# InkTime.net
KiCad netlist of a schematic drawn in EAGLE
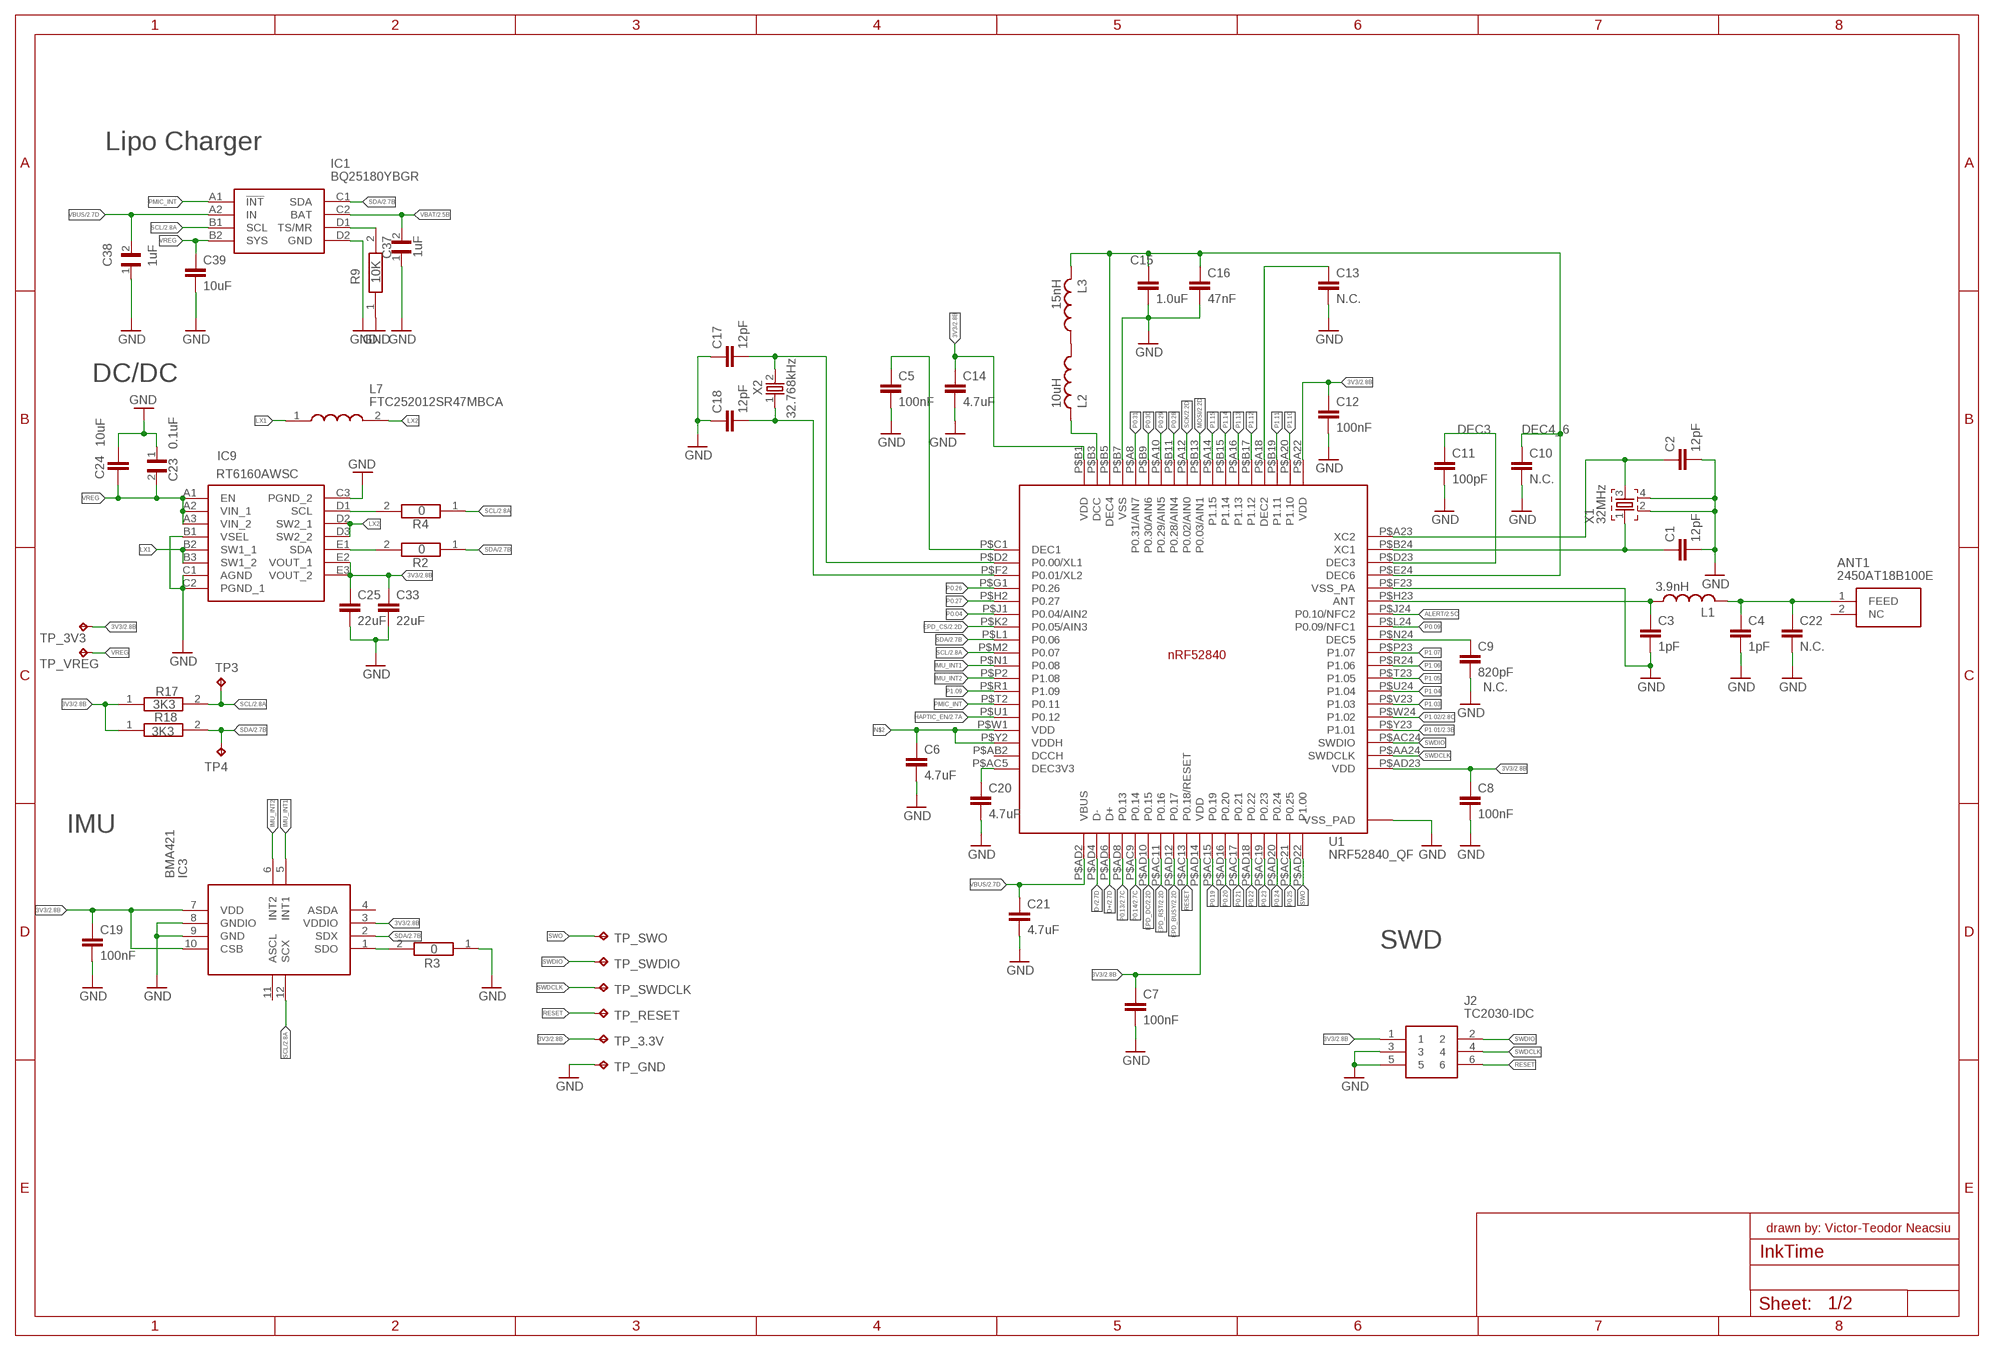
[diagram p0: schematic, sheet 1]
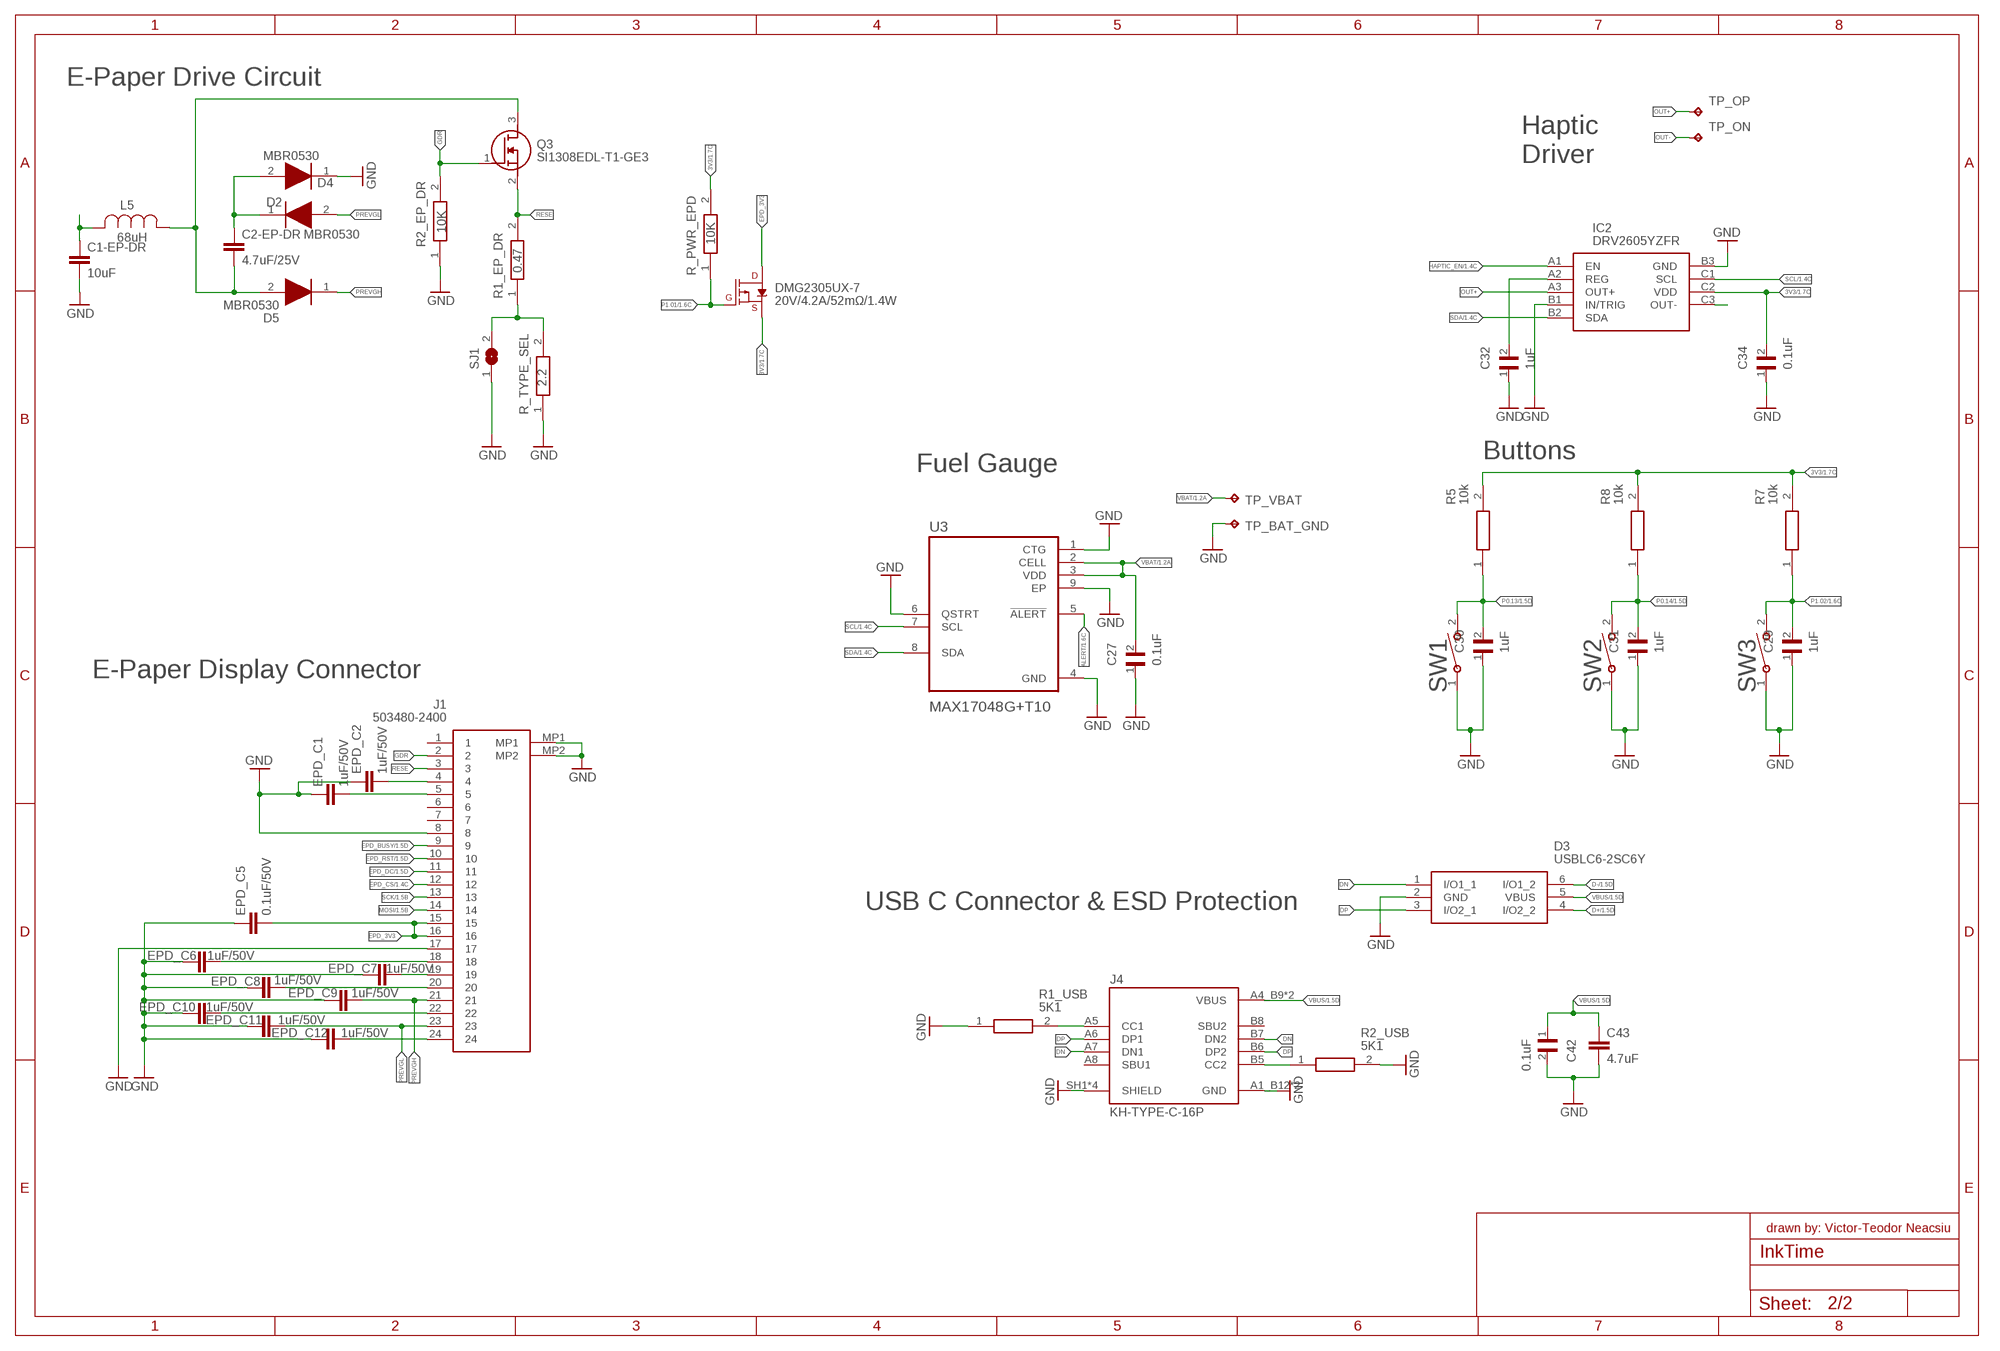
[diagram p1: schematic, sheet 2]

(export (version "E")
  (design (tool "Eeschema 10.0.6"))
  (components
    (comp (ref "C1-EP-DR")
      (value "10uF")
      (footprint "eagle-import:NORDIC_NRF_3_RESC0402_L")
      (libsource (lib "eagle-import") (part "NORDIC_NRF_3_CAPACITOR_0402_L"))
    )
    (comp (ref "C2-EP-DR")
      (value "4.7uF/25V")
      (footprint "eagle-import:NORDIC_NRF_3_RESC0402_L")
      (libsource (lib "eagle-import") (part "NORDIC_NRF_3_CAPACITOR_0402_L"))
    )
    (comp (ref "C27")
      (value "0.1uF")
      (footprint "eagle-import:GRM011R60J152KE01L_2_CAPC0201X13N")
      (fields (field (name "MF") "Murata") (field (name "MP") "GRM011R60J152KE01L"))
      (libsource (lib "eagle-import") (part "GRM011R60J152KE01L_2_GRM011R60J152KE01L"))
    )
    (comp (ref "C29")
      (value "1uF")
      (footprint "eagle-import:GRM011R60J152KE01L_2_CAPC0201X13N")
      (fields (field (name "MF") "Murata") (field (name "MP") "GRM011R60J152KE01L"))
      (libsource (lib "eagle-import") (part "GRM011R60J152KE01L_2_GRM011R60J152KE01L"))
    )
    (comp (ref "C30")
      (value "1uF")
      (footprint "eagle-import:GRM011R60J152KE01L_2_CAPC0201X13N")
      (fields (field (name "MF") "Murata") (field (name "MP") "GRM011R60J152KE01L"))
      (libsource (lib "eagle-import") (part "GRM011R60J152KE01L_2_GRM011R60J152KE01L"))
    )
    (comp (ref "C31")
      (value "1uF")
      (footprint "eagle-import:GRM011R60J152KE01L_2_CAPC0201X13N")
      (fields (field (name "MF") "Murata") (field (name "MP") "GRM011R60J152KE01L"))
      (libsource (lib "eagle-import") (part "GRM011R60J152KE01L_2_GRM011R60J152KE01L"))
    )
    (comp (ref "C32")
      (value "1uF")
      (footprint "eagle-import:GRM011R60J152KE01L_2_CAPC0201X13N")
      (fields (field (name "MF") "Murata") (field (name "MP") "GRM011R60J152KE01L"))
      (libsource (lib "eagle-import") (part "GRM011R60J152KE01L_2_GRM011R60J152KE01L"))
    )
    (comp (ref "C34")
      (value "0.1uF")
      (footprint "eagle-import:GRM011R60J152KE01L_2_CAPC0201X13N")
      (fields (field (name "MF") "Murata") (field (name "MP") "GRM011R60J152KE01L"))
      (libsource (lib "eagle-import") (part "GRM011R60J152KE01L_2_GRM011R60J152KE01L"))
    )
    (comp (ref "C42")
      (value "0.1uF")
      (footprint "eagle-import:GRM011R60J152KE01L_2_CAPC0201X13N")
      (fields (field (name "MF") "Murata") (field (name "MP") "GRM011R60J152KE01L"))
      (libsource (lib "eagle-import") (part "GRM011R60J152KE01L_2_GRM011R60J152KE01L"))
    )
    (comp (ref "C43")
      (value "4.7uF")
      (footprint "eagle-import:NORDIC_NRF_3_RESC0402_L")
      (libsource (lib "eagle-import") (part "NORDIC_NRF_3_CAPACITOR_0402_L"))
    )
    (comp (ref "D2")
      (value "MBR0530")
      (footprint "eagle-import:ESP32_C6_LIBRARY_5_SOD3716X135N")
      (fields (field (name "MF") "ON Semiconductor"))
      (libsource (lib "eagle-import") (part "ESP32_C6_LIBRARY_5_MBR0530"))
    )
    (comp (ref "D3")
      (value "USBLC6-2SC6Y")
      (footprint "eagle-import:ESP32_C6_LIBRARY_3_SOT95P280X145-6N")
      (fields (field (name "MF") "STMicroelectronics"))
      (libsource (lib "eagle-import") (part "ESP32_C6_LIBRARY_3_USBLC6-2SC6Y"))
    )
    (comp (ref "D4")
      (value "MBR0530")
      (footprint "eagle-import:ESP32_C6_LIBRARY_5_SOD3716X135N")
      (fields (field (name "MF") "ON Semiconductor"))
      (libsource (lib "eagle-import") (part "ESP32_C6_LIBRARY_5_MBR0530"))
    )
    (comp (ref "D5")
      (value "MBR0530")
      (footprint "eagle-import:ESP32_C6_LIBRARY_5_SOD3716X135N")
      (fields (field (name "MF") "ON Semiconductor"))
      (libsource (lib "eagle-import") (part "ESP32_C6_LIBRARY_5_MBR0530"))
    )
    (comp (ref "DMG2305UX-7")
      (value "20V/4.2A/52mΩ/1.4W")
      (footprint "eagle-import:ESP32_C6_LIBRARY_4_ESP32_C6_LIBRARY_4_ESP32_C6_LIBRARY_4_ESP32_C6_LIBRARY_4_ESP32_WROVER_SPARKFUN-DISCRETESEMI_SOT23-3")
      (libsource (lib "eagle-import") (part "ESP32_C6_LIBRARY_4_ESP32_WROVER_SPARKFUN-DISCRETESEMI_MOSFET_PCH-DMG2305UX-7"))
    )
    (comp (ref "EPD_C1")
      (value "1uF/50V")
      (footprint "eagle-import:NORDIC_NRF_3_RESC0402_L")
      (libsource (lib "eagle-import") (part "NORDIC_NRF_3_CAPACITOR_0402_L"))
    )
    (comp (ref "EPD_C2")
      (value "1uF/50V")
      (footprint "eagle-import:NORDIC_NRF_3_RESC0402_L")
      (libsource (lib "eagle-import") (part "NORDIC_NRF_3_CAPACITOR_0402_L"))
    )
    (comp (ref "EPD_C5")
      (value "0.1uF/50V")
      (footprint "eagle-import:NORDIC_NRF_3_RESC0402_L")
      (libsource (lib "eagle-import") (part "NORDIC_NRF_3_CAPACITOR_0402_L"))
    )
    (comp (ref "EPD_C6")
      (value "1uF/50V")
      (footprint "eagle-import:NORDIC_NRF_3_RESC0402_L")
      (libsource (lib "eagle-import") (part "NORDIC_NRF_3_CAPACITOR_0402_L"))
    )
    (comp (ref "EPD_C7")
      (value "1uF/50V")
      (footprint "eagle-import:NORDIC_NRF_3_RESC0402_L")
      (libsource (lib "eagle-import") (part "NORDIC_NRF_3_CAPACITOR_0402_L"))
    )
    (comp (ref "EPD_C8")
      (value "1uF/50V")
      (footprint "eagle-import:NORDIC_NRF_3_RESC0402_L")
      (libsource (lib "eagle-import") (part "NORDIC_NRF_3_CAPACITOR_0402_L"))
    )
    (comp (ref "EPD_C9")
      (value "1uF/50V")
      (footprint "eagle-import:NORDIC_NRF_3_RESC0402_L")
      (libsource (lib "eagle-import") (part "NORDIC_NRF_3_CAPACITOR_0402_L"))
    )
    (comp (ref "EPD_C10")
      (value "1uF/50V")
      (footprint "eagle-import:NORDIC_NRF_3_RESC0402_L")
      (libsource (lib "eagle-import") (part "NORDIC_NRF_3_CAPACITOR_0402_L"))
    )
    (comp (ref "EPD_C11")
      (value "1uF/50V")
      (footprint "eagle-import:NORDIC_NRF_3_RESC0402_L")
      (libsource (lib "eagle-import") (part "NORDIC_NRF_3_CAPACITOR_0402_L"))
    )
    (comp (ref "EPD_C12")
      (value "1uF/50V")
      (footprint "eagle-import:NORDIC_NRF_3_RESC0402_L")
      (libsource (lib "eagle-import") (part "NORDIC_NRF_3_CAPACITOR_0402_L"))
    )
    (comp (ref "IC2")
      (value "DRV2605YZFR")
      (footprint "eagle-import:DRV2605YZFR_BGA9C50P3X3_144X144X62")
      (libsource (lib "eagle-import") (part "DRV2605YZFR_DRV2605YZFR"))
    )
    (comp (ref "J1")
      (value "503480-2400")
      (footprint "eagle-import:503480-2400_5034802400")
      (fields (field (name "MOUSER_PART_NUMBER") "538-503480-2400"))
      (libsource (lib "eagle-import") (part "503480-2400_503480-2400"))
    )
    (comp (ref "J4")
      (value "KH-TYPE-C-16P")
      (footprint "eagle-import:KH-TYPE-C-16P_KINGHELM_KH-TYPE-C-16P")
      (fields (field (name "MF") "kinghelm"))
      (libsource (lib "eagle-import") (part "KH-TYPE-C-16P_KH-TYPE-C-16P"))
    )
    (comp (ref "L5")
      (value "68uH")
      (footprint "eagle-import:ESP32_C6_LIBRARY_2_IND_4828-WE-TPC_WRE")
      (fields
        (field (name "MANUFACTURER_PART_NUMBER") "744043680")
        (field (name "COPYRIGHT") "Copyright (C) 2024 Ultra Librarian. All rights reserved.")
      )
      (libsource (lib "eagle-import") (part "ESP32_C6_LIBRARY_2_744043680IND_4828-WE-TPC_WRE"))
    )
    (comp (ref "Q3")
      (value "SI1308EDL-T1-GE3")
      (footprint "eagle-import:ESP32_C6_LIBRARY_6_SOT65P210X110-3N")
      (fields (field (name "MF") "Vishay Siliconix"))
      (libsource (lib "eagle-import") (part "ESP32_C6_LIBRARY_6_SI1308EDL-T1-GE3"))
    )
    (comp (ref "R1_EP_DR")
      (value "0.47")
      (footprint "eagle-import:CPF0201D7K68C1_0201")
      (libsource (lib "eagle-import") (part "CPF0201D7K68C1_CPF0201D7K68C1"))
    )
    (comp (ref "R1_USB")
      (value "5K1")
      (footprint "eagle-import:CPF0201D7K68C1_0201")
      (libsource (lib "eagle-import") (part "CPF0201D7K68C1_CPF0201D7K68C1"))
    )
    (comp (ref "R2_EP_DR")
      (value "10K")
      (footprint "eagle-import:CPF0201D7K68C1_0201")
      (libsource (lib "eagle-import") (part "CPF0201D7K68C1_CPF0201D7K68C1"))
    )
    (comp (ref "R2_USB")
      (value "5K1")
      (footprint "eagle-import:CPF0201D7K68C1_0201")
      (libsource (lib "eagle-import") (part "CPF0201D7K68C1_CPF0201D7K68C1"))
    )
    (comp (ref "R5")
      (value "10k")
      (footprint "eagle-import:CPF0201D7K68C1_0201")
      (libsource (lib "eagle-import") (part "CPF0201D7K68C1_CPF0201D7K68C1"))
    )
    (comp (ref "R7")
      (value "10k")
      (footprint "eagle-import:CPF0201D7K68C1_0201")
      (libsource (lib "eagle-import") (part "CPF0201D7K68C1_CPF0201D7K68C1"))
    )
    (comp (ref "R8")
      (value "10k")
      (footprint "eagle-import:CPF0201D7K68C1_0201")
      (libsource (lib "eagle-import") (part "CPF0201D7K68C1_CPF0201D7K68C1"))
    )
    (comp (ref "R_PWR_EPD")
      (value "10K")
      (footprint "eagle-import:CPF0201D7K68C1_0201")
      (libsource (lib "eagle-import") (part "CPF0201D7K68C1_CPF0201D7K68C1"))
    )
    (comp (ref "R_TYPE_SEL")
      (value "2.2")
      (footprint "eagle-import:CPF0201D7K68C1_0201")
      (libsource (lib "eagle-import") (part "CPF0201D7K68C1_CPF0201D7K68C1"))
    )
    (comp (ref "SJ1")
      (value "ESP32_C6_LIBRARY_7_JUMPER_SJ")
      (footprint "eagle-import:ESP32_C6_LIBRARY_7_JUMPER_SJ")
      (libsource (lib "eagle-import") (part "ESP32_C6_LIBRARY_7_JUMPER_SJ"))
    )
    (comp (ref "SW1")
      (value "2025-10-22_07-23-44_LIBRARY_EVP-AKE31ASW_EVP-AKE31A_PAN")
      (footprint "eagle-import:2025-10-22_07-23-44_LIBRARY_SW_EVP-AKE31A_PAN")
      (fields
        (field (name "MANUFACTURER_PART_NUMBER") "EVP-AKE31A")
        (field (name "COPYRIGHT") "Copyright (C) 2025 Ultra Librarian. All rights reserved.")
      )
      (libsource (lib "eagle-import") (part "2025-10-22_07-23-44_LIBRARY_EVP-AKE31ASW_EVP-AKE31A_PAN"))
    )
    (comp (ref "SW2")
      (value "2025-10-22_07-23-44_LIBRARY_EVP-AKE31ASW_EVP-AKE31A_PAN")
      (footprint "eagle-import:2025-10-22_07-23-44_LIBRARY_SW_EVP-AKE31A_PAN")
      (fields
        (field (name "MANUFACTURER_PART_NUMBER") "EVP-AKE31A")
        (field (name "COPYRIGHT") "Copyright (C) 2025 Ultra Librarian. All rights reserved.")
      )
      (libsource (lib "eagle-import") (part "2025-10-22_07-23-44_LIBRARY_EVP-AKE31ASW_EVP-AKE31A_PAN"))
    )
    (comp (ref "SW3")
      (value "2025-10-22_07-23-44_LIBRARY_EVP-AKE31ASW_EVP-AKE31A_PAN")
      (footprint "eagle-import:2025-10-22_07-23-44_LIBRARY_SW_EVP-AKE31A_PAN")
      (fields
        (field (name "MANUFACTURER_PART_NUMBER") "EVP-AKE31A")
        (field (name "COPYRIGHT") "Copyright (C) 2025 Ultra Librarian. All rights reserved.")
      )
      (libsource (lib "eagle-import") (part "2025-10-22_07-23-44_LIBRARY_EVP-AKE31ASW_EVP-AKE31A_PAN"))
    )
    (comp (ref "TP_BAT_GND")
      (value "HECTOR_WATCH_1_TPTP20R")
      (footprint "eagle-import:HECTOR_WATCH_1_TP20R")
      (libsource (lib "eagle-import") (part "HECTOR_WATCH_1_TPTP20R"))
    )
    (comp (ref "TP_ON")
      (value "HECTOR_WATCH_1_TPTP20R")
      (footprint "eagle-import:HECTOR_WATCH_1_TP20R")
      (libsource (lib "eagle-import") (part "HECTOR_WATCH_1_TPTP20R"))
    )
    (comp (ref "TP_OP")
      (value "HECTOR_WATCH_1_TPTP20R")
      (footprint "eagle-import:HECTOR_WATCH_1_TP20R")
      (libsource (lib "eagle-import") (part "HECTOR_WATCH_1_TPTP20R"))
    )
    (comp (ref "TP_VBAT")
      (value "HECTOR_WATCH_1_TPTP20R")
      (footprint "eagle-import:HECTOR_WATCH_1_TP20R")
      (libsource (lib "eagle-import") (part "HECTOR_WATCH_1_TPTP20R"))
    )
    (comp (ref "U3")
      (value "MAX17048G+T10")
      (footprint "eagle-import:ESP32_C6_LIBRARY_SON50P200X200X80-9N")
      (fields (field (name "MF") "Analog Devices"))
      (libsource (lib "eagle-import") (part "ESP32_C6_LIBRARY_MAX17048G+T10"))
    )
    (comp (ref "ANT1")
      (value "2450AT18B100E")
      (footprint "eagle-import:2450AT18B100E_ANTC3216X140N")
      (fields (field (name "MOUSER_PART_NUMBER") "609-2450AT18B100E"))
      (libsource (lib "eagle-import") (part "2450AT18B100E_2450AT18B100E"))
    )
    (comp (ref "C1")
      (value "12pF")
      (footprint "eagle-import:NORDIC_NRF_3_RESC0201_L")
      (libsource (lib "eagle-import") (part "NORDIC_NRF_3_CAPACITOR_0201_L"))
    )
    (comp (ref "C2")
      (value "12pF")
      (footprint "eagle-import:NORDIC_NRF_3_RESC0201_L")
      (libsource (lib "eagle-import") (part "NORDIC_NRF_3_CAPACITOR_0201_L"))
    )
    (comp (ref "C3")
      (value "1pF")
      (footprint "eagle-import:NORDIC_NRF_3_RESC0201_L")
      (libsource (lib "eagle-import") (part "NORDIC_NRF_3_CAPACITOR_0201_L"))
    )
    (comp (ref "C4")
      (value "1pF")
      (footprint "eagle-import:NORDIC_NRF_3_RESC0201_L")
      (libsource (lib "eagle-import") (part "NORDIC_NRF_3_CAPACITOR_0201_L"))
    )
    (comp (ref "C5")
      (value "100nF")
      (footprint "eagle-import:NORDIC_NRF_3_RESC0402_L")
      (libsource (lib "eagle-import") (part "NORDIC_NRF_3_CAPACITOR_0402_L"))
    )
    (comp (ref "C6")
      (value "4.7uF")
      (footprint "eagle-import:NORDIC_NRF_3_RESC0402_L")
      (libsource (lib "eagle-import") (part "NORDIC_NRF_3_CAPACITOR_0402_L"))
    )
    (comp (ref "C7")
      (value "100nF")
      (footprint "eagle-import:NORDIC_NRF_3_RESC0402_L")
      (libsource (lib "eagle-import") (part "NORDIC_NRF_3_CAPACITOR_0402_L"))
    )
    (comp (ref "C8")
      (value "100nF")
      (footprint "eagle-import:NORDIC_NRF_3_RESC0402_L")
      (libsource (lib "eagle-import") (part "NORDIC_NRF_3_CAPACITOR_0402_L"))
    )
    (comp (ref "C9")
      (value "820pF")
      (footprint "eagle-import:NORDIC_NRF_3_RESC0201_L")
      (libsource (lib "eagle-import") (part "NORDIC_NRF_3_CAPACITOR_0201_L"))
    )
    (comp (ref "C10")
      (value "N.C.")
      (footprint "eagle-import:NORDIC_NRF_3_RESC0201_L")
      (libsource (lib "eagle-import") (part "NORDIC_NRF_3_CAPACITOR_0201_L"))
    )
    (comp (ref "C11")
      (value "100pF")
      (footprint "eagle-import:NORDIC_NRF_3_RESC0201_L")
      (libsource (lib "eagle-import") (part "NORDIC_NRF_3_CAPACITOR_0201_L"))
    )
    (comp (ref "C12")
      (value "100nF")
      (footprint "eagle-import:NORDIC_NRF_3_RESC0402_L")
      (libsource (lib "eagle-import") (part "NORDIC_NRF_3_CAPACITOR_0402_L"))
    )
    (comp (ref "C13")
      (value "N.C.")
      (footprint "eagle-import:NORDIC_NRF_3_RESC0201_L")
      (libsource (lib "eagle-import") (part "NORDIC_NRF_3_CAPACITOR_0201_L"))
    )
    (comp (ref "C14")
      (value "4.7uF")
      (footprint "eagle-import:NORDIC_NRF_3_RESC0402_L")
      (libsource (lib "eagle-import") (part "NORDIC_NRF_3_CAPACITOR_0402_L"))
    )
    (comp (ref "C15")
      (value "1.0uF")
      (footprint "eagle-import:NORDIC_NRF_3_RESC0402_L")
      (libsource (lib "eagle-import") (part "NORDIC_NRF_3_CAPACITOR_0402_L"))
    )
    (comp (ref "C16")
      (value "47nF")
      (footprint "eagle-import:NORDIC_NRF_3_RESC0201_L")
      (libsource (lib "eagle-import") (part "NORDIC_NRF_3_CAPACITOR_0201_L"))
    )
    (comp (ref "C17")
      (value "12pF")
      (footprint "eagle-import:NORDIC_NRF_3_RESC0201_L")
      (libsource (lib "eagle-import") (part "NORDIC_NRF_3_CAPACITOR_0201_L"))
    )
    (comp (ref "C18")
      (value "12pF")
      (footprint "eagle-import:NORDIC_NRF_3_RESC0201_L")
      (libsource (lib "eagle-import") (part "NORDIC_NRF_3_CAPACITOR_0201_L"))
    )
    (comp (ref "C19")
      (value "100nF")
      (footprint "eagle-import:NORDIC_NRF_3_RESC0402_L")
      (libsource (lib "eagle-import") (part "NORDIC_NRF_3_CAPACITOR_0402_L"))
    )
    (comp (ref "C20")
      (value "4.7uF")
      (footprint "eagle-import:NORDIC_NRF_3_RESC0402_L")
      (libsource (lib "eagle-import") (part "NORDIC_NRF_3_CAPACITOR_0402_L"))
    )
    (comp (ref "C21")
      (value "4.7uF")
      (footprint "eagle-import:NORDIC_NRF_3_RESC0402_L")
      (libsource (lib "eagle-import") (part "NORDIC_NRF_3_CAPACITOR_0402_L"))
    )
    (comp (ref "C22")
      (value "N.C.")
      (footprint "eagle-import:NORDIC_NRF_3_RESC0201_L")
      (libsource (lib "eagle-import") (part "NORDIC_NRF_3_CAPACITOR_0201_L"))
    )
    (comp (ref "C23")
      (value "0.1uF")
      (footprint "eagle-import:GRM011R60J152KE01L_2_CAPC0201X13N")
      (fields (field (name "MF") "Murata") (field (name "MP") "GRM011R60J152KE01L"))
      (libsource (lib "eagle-import") (part "GRM011R60J152KE01L_2_GRM011R60J152KE01L"))
    )
    (comp (ref "C24")
      (value "10uF")
      (footprint "eagle-import:NORDIC_NRF_3_RESC0201_L")
      (libsource (lib "eagle-import") (part "NORDIC_NRF_3_CAPACITOR_0201_L"))
    )
    (comp (ref "C25")
      (value "22uF")
      (footprint "eagle-import:NORDIC_NRF_3_RESC0402_L")
      (libsource (lib "eagle-import") (part "NORDIC_NRF_3_CAPACITOR_0402_L"))
    )
    (comp (ref "C33")
      (value "22uF")
      (footprint "eagle-import:NORDIC_NRF_3_RESC0402_L")
      (libsource (lib "eagle-import") (part "NORDIC_NRF_3_CAPACITOR_0402_L"))
    )
    (comp (ref "C37")
      (value "1uF")
      (footprint "eagle-import:GRM011R60J152KE01L_2_CAPC0201X13N")
      (fields (field (name "MF") "Murata") (field (name "MP") "GRM011R60J152KE01L"))
      (libsource (lib "eagle-import") (part "GRM011R60J152KE01L_2_GRM011R60J152KE01L"))
    )
    (comp (ref "C38")
      (value "1uF")
      (footprint "eagle-import:GRM011R60J152KE01L_2_CAPC0201X13N")
      (fields (field (name "MF") "Murata") (field (name "MP") "GRM011R60J152KE01L"))
      (libsource (lib "eagle-import") (part "GRM011R60J152KE01L_2_GRM011R60J152KE01L"))
    )
    (comp (ref "C39")
      (value "10uF")
      (footprint "eagle-import:NORDIC_NRF_3_RESC0402_L")
      (libsource (lib "eagle-import") (part "NORDIC_NRF_3_CAPACITOR_0402_L"))
    )
    (comp (ref "IC1")
      (value "BQ25180YBGR")
      (footprint "eagle-import:BQ25180YBGR_BGA8C40P2X4_100X155X50")
      (fields (field (name "MOUSER_PART_NUMBER") "595-BQ25180YBGR"))
      (libsource (lib "eagle-import") (part "BQ25180YBGR_BQ25180YBGR"))
    )
    (comp (ref "IC3")
      (value "BMA421")
      (footprint "eagle-import:BMA423_BMA423")
      (fields (field (name "ARROW_PART_NUMBER") "BMA423") (field (name "MOUSER_PART_NUMBER") "262-BMA423"))
      (libsource (lib "eagle-import") (part "BMA423_BMA423"))
    )
    (comp (ref "IC9")
      (value "RT6160AWSC")
      (footprint "eagle-import:RT6160AWSC_BGA15C40P3X5_140X230X60")
      (fields (field (name "MOUSER_PART_NUMBER") "835-RT6160AWSC"))
      (libsource (lib "eagle-import") (part "RT6160AWSC_RT6160AWSC"))
    )
    (comp (ref "J2")
      (value "TC2030-IDC")
      (footprint "eagle-import:TC2030-IDC_TC2030IDC")
      (libsource (lib "eagle-import") (part "TC2030-IDC_TC2030-IDC"))
    )
    (comp (ref "L1")
      (value "3.9nH")
      (footprint "eagle-import:NORDIC_NRF_2_RESC0402_L")
      (libsource (lib "eagle-import") (part "NORDIC_NRF_2_INDUCTOR_0402_L"))
    )
    (comp (ref "L2")
      (value "10uH")
      (footprint "eagle-import:NORDIC_NRF_2_RESC0402_L")
      (libsource (lib "eagle-import") (part "NORDIC_NRF_2_INDUCTOR_0402_L"))
    )
    (comp (ref "L3")
      (value "15nH")
      (footprint "eagle-import:NORDIC_NRF_2_RESC0201_L")
      (libsource (lib "eagle-import") (part "NORDIC_NRF_2_INDUCTOR_0201_L"))
    )
    (comp (ref "L7")
      (value "FTC252012SR47MBCA")
      (footprint "eagle-import:MLP2016SR47MT0S1_INDC2016X100N")
      (libsource (lib "eagle-import") (part "MLP2016SR47MT0S1_FTC252012SR47MBCA"))
    )
    (comp (ref "R2")
      (value "0")
      (footprint "eagle-import:CPF0201D7K68C1_0201")
      (libsource (lib "eagle-import") (part "CPF0201D7K68C1_CPF0201D7K68C1"))
    )
    (comp (ref "R3")
      (value "0")
      (footprint "eagle-import:ERA-1AEB3401C_0201")
      (libsource (lib "eagle-import") (part "ERA-1AEB3401C_CPF0201D7K68C1"))
    )
    (comp (ref "R4")
      (value "0")
      (footprint "eagle-import:CPF0201D7K68C1_0201")
      (libsource (lib "eagle-import") (part "CPF0201D7K68C1_CPF0201D7K68C1"))
    )
    (comp (ref "R9")
      (value "10K")
      (footprint "eagle-import:CPF0201D7K68C1_0201")
      (libsource (lib "eagle-import") (part "CPF0201D7K68C1_CPF0201D7K68C1"))
    )
    (comp (ref "R17")
      (value "3K3")
      (footprint "eagle-import:CPF0201D7K68C1_0201")
      (libsource (lib "eagle-import") (part "CPF0201D7K68C1_CPF0201D7K68C1"))
    )
    (comp (ref "R18")
      (value "3K3")
      (footprint "eagle-import:CPF0201D7K68C1_0201")
      (libsource (lib "eagle-import") (part "CPF0201D7K68C1_CPF0201D7K68C1"))
    )
    (comp (ref "TP3")
      (value "HECTOR_WATCH_1_TPTP20R")
      (footprint "eagle-import:HECTOR_WATCH_1_TP20R")
      (libsource (lib "eagle-import") (part "HECTOR_WATCH_1_TPTP20R"))
    )
    (comp (ref "TP4")
      (value "HECTOR_WATCH_1_TPTP20R")
      (footprint "eagle-import:HECTOR_WATCH_1_TP20R")
      (libsource (lib "eagle-import") (part "HECTOR_WATCH_1_TPTP20R"))
    )
    (comp (ref "TP_3.3V")
      (value "HECTOR_WATCH_1_TPTP20R")
      (footprint "eagle-import:HECTOR_WATCH_1_TP20R")
      (libsource (lib "eagle-import") (part "HECTOR_WATCH_1_TPTP20R"))
    )
    (comp (ref "TP_3V3")
      (value "HECTOR_WATCH_1_TPTP20R")
      (footprint "eagle-import:HECTOR_WATCH_1_TP20R")
      (libsource (lib "eagle-import") (part "HECTOR_WATCH_1_TPTP20R"))
    )
    (comp (ref "TP_GND")
      (value "HECTOR_WATCH_1_TPTP20R")
      (footprint "eagle-import:HECTOR_WATCH_1_TP20R")
      (libsource (lib "eagle-import") (part "HECTOR_WATCH_1_TPTP20R"))
    )
    (comp (ref "TP_RESET")
      (value "HECTOR_WATCH_1_TPTP20R")
      (footprint "eagle-import:HECTOR_WATCH_1_TP20R")
      (libsource (lib "eagle-import") (part "HECTOR_WATCH_1_TPTP20R"))
    )
    (comp (ref "TP_SWDCLK")
      (value "HECTOR_WATCH_1_TPTP20R")
      (footprint "eagle-import:HECTOR_WATCH_1_TP20R")
      (libsource (lib "eagle-import") (part "HECTOR_WATCH_1_TPTP20R"))
    )
    (comp (ref "TP_SWDIO")
      (value "HECTOR_WATCH_1_TPTP20R")
      (footprint "eagle-import:HECTOR_WATCH_1_TP20R")
      (libsource (lib "eagle-import") (part "HECTOR_WATCH_1_TPTP20R"))
    )
    (comp (ref "TP_SWO")
      (value "HECTOR_WATCH_1_TPTP20R")
      (footprint "eagle-import:HECTOR_WATCH_1_TP20R")
      (libsource (lib "eagle-import") (part "HECTOR_WATCH_1_TPTP20R"))
    )
    (comp (ref "TP_VREG")
      (value "HECTOR_WATCH_1_TPTP20R")
      (footprint "eagle-import:HECTOR_WATCH_1_TP20R")
      (libsource (lib "eagle-import") (part "HECTOR_WATCH_1_TPTP20R"))
    )
    (comp (ref "U1")
      (value "NRF52840_QF")
      (footprint "eagle-import:NORDIC_NRF_4_AQFN50P700X700X85_HS-74N")
      (libsource (lib "eagle-import") (part "NORDIC_NRF_4_NRF52840_QF"))
    )
    (comp (ref "X1")
      (value "32MHz")
      (footprint "eagle-import:NORDIC_NRF_BT-XTAL_2016_N")
      (libsource (lib "eagle-import") (part "NORDIC_NRF_XTAL_32MHZ"))
    )
    (comp (ref "X2")
      (value "32.768kHz")
      (footprint "eagle-import:NORDIC_NRF_1_XTAL_3215_N")
      (libsource (lib "eagle-import") (part "NORDIC_NRF_1_XTAL_32KHZ"))
    )
  )
  (nets
    (net (code "1") (name "3V3") (class "Default")
      (node (ref "C12") (pin "1") (pinfunction "1_1") (pintype "passive"))
      (node (ref "C14") (pin "1") (pinfunction "1_1") (pintype "passive"))
      (node (ref "C19") (pin "1") (pinfunction "1_1") (pintype "passive"))
      (node (ref "C25") (pin "1") (pinfunction "1_1") (pintype "passive"))
      (node (ref "C33") (pin "1") (pinfunction "1_1") (pintype "passive"))
      (node (ref "C34") (pin "2") (pinfunction "2_2") (pintype "passive"))
      (node (ref "C7") (pin "1") (pinfunction "1_1") (pintype "passive"))
      (node (ref "C8") (pin "1") (pinfunction "1_1") (pintype "passive"))
      (node (ref "DMG2305UX-7") (pin "2") (pinfunction "S_2") (pintype "bidirectional"))
      (node (ref "IC2") (pin "C2") (pinfunction "VDD_C2") (pintype "bidirectional"))
      (node (ref "IC3") (pin "10") (pinfunction "CSB_10") (pintype "bidirectional"))
      (node (ref "IC3") (pin "3") (pinfunction "VDDIO_3") (pintype "bidirectional"))
      (node (ref "IC3") (pin "7") (pinfunction "VDD_7") (pintype "bidirectional"))
      (node (ref "IC9") (pin "E2") (pinfunction "VOUT_1_E2") (pintype "bidirectional"))
      (node (ref "IC9") (pin "E3") (pinfunction "VOUT_2_E3") (pintype "bidirectional"))
      (node (ref "J2") (pin "1") (pinfunction "1_1") (pintype "bidirectional"))
      (node (ref "R17") (pin "1") (pinfunction "1_1") (pintype "bidirectional"))
      (node (ref "R18") (pin "1") (pinfunction "1_1") (pintype "bidirectional"))
      (node (ref "R5") (pin "2") (pinfunction "2_2") (pintype "bidirectional"))
      (node (ref "R7") (pin "2") (pinfunction "2_2") (pintype "bidirectional"))
      (node (ref "R8") (pin "2") (pinfunction "2_2") (pintype "bidirectional"))
      (node (ref "R_PWR_EPD") (pin "2") (pinfunction "2_2") (pintype "bidirectional"))
      (node (ref "TP_3.3V") (pin "TP") (pinfunction "TP_TP") (pintype "input"))
      (node (ref "TP_3V3") (pin "TP") (pinfunction "TP_TP") (pintype "input"))
      (node (ref "U1") (pin "P$A22") (pinfunction "VDD_P$A22") (pintype "power_in"))
      (node (ref "U1") (pin "P$AD14") (pinfunction "VDD_P$AD14") (pintype "power_in"))
      (node (ref "U1") (pin "P$AD23") (pinfunction "VDD_P$AD23") (pintype "power_in"))
      (node (ref "U1") (pin "P$B1") (pinfunction "VDD_P$B1") (pintype "power_in"))
    )
    (net (code "2") (name "ALERT") (class "Default")
      (node (ref "U1") (pin "P$J24") (pinfunction "P0.10/NFC2_P$J24") (pintype "bidirectional"))
      (node (ref "U3") (pin "5") (pinfunction "~{ALERT}_5") (pintype "output"))
    )
    (net (code "3") (name "D+") (class "Default")
      (node (ref "D3") (pin "4") (pinfunction "I/O2_2_4") (pintype "bidirectional"))
      (node (ref "U1") (pin "P$AD6") (pinfunction "D+_P$AD6") (pintype "bidirectional"))
    )
    (net (code "4") (name "D-") (class "Default")
      (node (ref "D3") (pin "6") (pinfunction "I/O1_2_6") (pintype "bidirectional"))
      (node (ref "U1") (pin "P$AD4") (pinfunction "D-_P$AD4") (pintype "bidirectional"))
    )
    (net (code "5") (name "DN") (class "Default")
      (node (ref "D3") (pin "1") (pinfunction "I/O1_1_1") (pintype "bidirectional"))
      (node (ref "J4") (pin "A7") (pinfunction "DN1_A7") (pintype "bidirectional"))
      (node (ref "J4") (pin "B7") (pinfunction "DN2_B7") (pintype "bidirectional"))
    )
    (net (code "6") (name "DP") (class "Default")
      (node (ref "D3") (pin "3") (pinfunction "I/O2_1_3") (pintype "bidirectional"))
      (node (ref "J4") (pin "A6") (pinfunction "DP1_A6") (pintype "bidirectional"))
      (node (ref "J4") (pin "B6") (pinfunction "DP2_B6") (pintype "bidirectional"))
    )
    (net (code "7") (name "EPD_3V3") (class "Default")
      (node (ref "DMG2305UX-7") (pin "3") (pinfunction "D_3") (pintype "bidirectional"))
      (node (ref "EPD_C5") (pin "2") (pinfunction "2_2") (pintype "passive"))
      (node (ref "J1") (pin "15") (pinfunction "15_15") (pintype "bidirectional"))
      (node (ref "J1") (pin "16") (pinfunction "16_16") (pintype "bidirectional"))
    )
    (net (code "8") (name "EPD_BUSY") (class "Default")
      (node (ref "J1") (pin "9") (pinfunction "9_9") (pintype "bidirectional"))
      (node (ref "U1") (pin "P$AD12") (pinfunction "P0.17_P$AD12") (pintype "bidirectional"))
    )
    (net (code "9") (name "EPD_CS") (class "Default")
      (node (ref "J1") (pin "12") (pinfunction "12_12") (pintype "bidirectional"))
      (node (ref "U1") (pin "P$K2") (pinfunction "P0.05/AIN3_P$K2") (pintype "bidirectional"))
    )
    (net (code "10") (name "EPD_DC") (class "Default")
      (node (ref "J1") (pin "11") (pinfunction "11_11") (pintype "bidirectional"))
      (node (ref "U1") (pin "P$AD10") (pinfunction "P0.15_P$AD10") (pintype "bidirectional"))
    )
    (net (code "11") (name "EPD_RST") (class "Default")
      (node (ref "J1") (pin "10") (pinfunction "10_10") (pintype "bidirectional"))
      (node (ref "U1") (pin "P$AC11") (pinfunction "P0.16_P$AC11") (pintype "bidirectional"))
    )
    (net (code "12") (name "GDR") (class "Default")
      (node (ref "J1") (pin "2") (pinfunction "2_2") (pintype "bidirectional"))
      (node (ref "Q3") (pin "1") (pinfunction "G_1") (pintype "bidirectional"))
      (node (ref "R2_EP_DR") (pin "2") (pinfunction "2_2") (pintype "bidirectional"))
    )
    (net (code "13") (name "GND") (class "Default")
      (node (ref "C1") (pin "2") (pinfunction "2_2") (pintype "passive"))
      (node (ref "C1-EP-DR") (pin "2") (pinfunction "2_2") (pintype "passive"))
      (node (ref "C10") (pin "2") (pinfunction "2_2") (pintype "passive"))
      (node (ref "C11") (pin "2") (pinfunction "2_2") (pintype "passive"))
      (node (ref "C12") (pin "2") (pinfunction "2_2") (pintype "passive"))
      (node (ref "C13") (pin "2") (pinfunction "2_2") (pintype "passive"))
      (node (ref "C14") (pin "2") (pinfunction "2_2") (pintype "passive"))
      (node (ref "C15") (pin "2") (pinfunction "2_2") (pintype "passive"))
      (node (ref "C16") (pin "2") (pinfunction "2_2") (pintype "passive"))
      (node (ref "C17") (pin "1") (pinfunction "1_1") (pintype "passive"))
      (node (ref "C18") (pin "1") (pinfunction "1_1") (pintype "passive"))
      (node (ref "C19") (pin "2") (pinfunction "2_2") (pintype "passive"))
      (node (ref "C2") (pin "2") (pinfunction "2_2") (pintype "passive"))
      (node (ref "C20") (pin "2") (pinfunction "2_2") (pintype "passive"))
      (node (ref "C21") (pin "2") (pinfunction "2_2") (pintype "passive"))
      (node (ref "C22") (pin "2") (pinfunction "2_2") (pintype "passive"))
      (node (ref "C23") (pin "1") (pinfunction "1_1") (pintype "passive"))
      (node (ref "C24") (pin "1") (pinfunction "1_1") (pintype "passive"))
      (node (ref "C25") (pin "2") (pinfunction "2_2") (pintype "passive"))
      (node (ref "C27") (pin "1") (pinfunction "1_1") (pintype "passive"))
      (node (ref "C29") (pin "1") (pinfunction "1_1") (pintype "passive"))
      (node (ref "C3") (pin "2") (pinfunction "2_2") (pintype "passive"))
      (node (ref "C30") (pin "1") (pinfunction "1_1") (pintype "passive"))
      (node (ref "C31") (pin "1") (pinfunction "1_1") (pintype "passive"))
      (node (ref "C32") (pin "1") (pinfunction "1_1") (pintype "passive"))
      (node (ref "C33") (pin "2") (pinfunction "2_2") (pintype "passive"))
      (node (ref "C34") (pin "1") (pinfunction "1_1") (pintype "passive"))
      (node (ref "C37") (pin "1") (pinfunction "1_1") (pintype "passive"))
      (node (ref "C38") (pin "1") (pinfunction "1_1") (pintype "passive"))
      (node (ref "C39") (pin "2") (pinfunction "2_2") (pintype "passive"))
      (node (ref "C4") (pin "2") (pinfunction "2_2") (pintype "passive"))
      (node (ref "C42") (pin "2") (pinfunction "2_2") (pintype "passive"))
      (node (ref "C43") (pin "2") (pinfunction "2_2") (pintype "passive"))
      (node (ref "C5") (pin "2") (pinfunction "2_2") (pintype "passive"))
      (node (ref "C6") (pin "2") (pinfunction "2_2") (pintype "passive"))
      (node (ref "C7") (pin "2") (pinfunction "2_2") (pintype "passive"))
      (node (ref "C8") (pin "2") (pinfunction "2_2") (pintype "passive"))
      (node (ref "C9") (pin "2") (pinfunction "2_2") (pintype "passive"))
      (node (ref "D3") (pin "2") (pinfunction "GND_2") (pintype "bidirectional"))
      (node (ref "D4") (pin "1") (pinfunction "K_1") (pintype "bidirectional"))
      (node (ref "EPD_C1") (pin "1") (pinfunction "1_1") (pintype "passive"))
      (node (ref "EPD_C10") (pin "1") (pinfunction "1_1") (pintype "passive"))
      (node (ref "EPD_C11") (pin "2") (pinfunction "2_2") (pintype "passive"))
      (node (ref "EPD_C12") (pin "2") (pinfunction "2_2") (pintype "passive"))
      (node (ref "EPD_C2") (pin "1") (pinfunction "1_1") (pintype "passive"))
      (node (ref "EPD_C5") (pin "1") (pinfunction "1_1") (pintype "passive"))
      (node (ref "EPD_C6") (pin "1") (pinfunction "1_1") (pintype "passive"))
      (node (ref "EPD_C7") (pin "2") (pinfunction "2_2") (pintype "passive"))
      (node (ref "EPD_C8") (pin "2") (pinfunction "2_2") (pintype "passive"))
      (node (ref "EPD_C9") (pin "2") (pinfunction "2_2") (pintype "passive"))
      (node (ref "IC1") (pin "D2") (pinfunction "GND_D2") (pintype "bidirectional"))
      (node (ref "IC2") (pin "B1") (pinfunction "IN/TRIG_B1") (pintype "bidirectional"))
      (node (ref "IC2") (pin "B3") (pinfunction "GND_B3") (pintype "bidirectional"))
      (node (ref "IC3") (pin "8") (pinfunction "GNDIO_8") (pintype "bidirectional"))
      (node (ref "IC3") (pin "9") (pinfunction "GND_9") (pintype "bidirectional"))
      (node (ref "IC9") (pin "B1") (pinfunction "VSEL_B1") (pintype "bidirectional"))
      (node (ref "IC9") (pin "C1") (pinfunction "AGND_C1") (pintype "bidirectional"))
      (node (ref "IC9") (pin "C2") (pinfunction "PGND_1_C2") (pintype "bidirectional"))
      (node (ref "IC9") (pin "C3") (pinfunction "PGND_2_C3") (pintype "bidirectional"))
      (node (ref "J1") (pin "17") (pinfunction "17_17") (pintype "bidirectional"))
      (node (ref "J1") (pin "8") (pinfunction "8_8") (pintype "bidirectional"))
      (node (ref "J1") (pin "MP1") (pinfunction "MP1_MP1") (pintype "bidirectional"))
      (node (ref "J1") (pin "MP2") (pinfunction "MP2_MP2") (pintype "bidirectional"))
      (node (ref "J2") (pin "3") (pinfunction "3_3") (pintype "bidirectional"))
      (node (ref "J2") (pin "5") (pinfunction "5_5") (pintype "bidirectional"))
      (node (ref "J4") (pin "A12_B1") (pinfunction "GND_A12_B1") (pintype "power_in"))
      (node (ref "J4") (pin "A1_B12") (pinfunction "GND_A1_B12") (pintype "power_in"))
      (node (ref "J4") (pin "SH1") (pinfunction "SHIELD_SH1") (pintype "passive"))
      (node (ref "J4") (pin "SH2") (pinfunction "SHIELD_SH2") (pintype "passive"))
      (node (ref "J4") (pin "SH3") (pinfunction "SHIELD_SH3") (pintype "passive"))
      (node (ref "J4") (pin "SH4") (pinfunction "SHIELD_SH4") (pintype "passive"))
      (node (ref "R1_USB") (pin "1") (pinfunction "1_1") (pintype "bidirectional"))
      (node (ref "R2_EP_DR") (pin "1") (pinfunction "1_1") (pintype "bidirectional"))
      (node (ref "R2_USB") (pin "2") (pinfunction "2_2") (pintype "bidirectional"))
      (node (ref "R3") (pin "1") (pinfunction "1_1") (pintype "bidirectional"))
      (node (ref "R9") (pin "1") (pinfunction "1_1") (pintype "bidirectional"))
      (node (ref "R_TYPE_SEL") (pin "1") (pinfunction "1_1") (pintype "bidirectional"))
      (node (ref "SJ1") (pin "1") (pinfunction "1_1") (pintype "passive"))
      (node (ref "SW1") (pin "1") (pinfunction "1_1") (pintype "passive"))
      (node (ref "SW2") (pin "1") (pinfunction "1_1") (pintype "passive"))
      (node (ref "SW3") (pin "1") (pinfunction "1_1") (pintype "passive"))
      (node (ref "TP_BAT_GND") (pin "TP") (pinfunction "TP_TP") (pintype "input"))
      (node (ref "TP_GND") (pin "TP") (pinfunction "TP_TP") (pintype "input"))
      (node (ref "U1") (pin "P$74") (pinfunction "VSS_PAD_P$74") (pintype "bidirectional"))
      (node (ref "U1") (pin "P$75") (pinfunction "VSS_PAD_P$75") (pintype "bidirectional"))
      (node (ref "U1") (pin "P$76") (pinfunction "VSS_PAD_P$76") (pintype "bidirectional"))
      (node (ref "U1") (pin "P$77") (pinfunction "VSS_PAD_P$77") (pintype "bidirectional"))
      (node (ref "U1") (pin "P$78") (pinfunction "VSS_PAD_P$78") (pintype "bidirectional"))
      (node (ref "U1") (pin "P$79") (pinfunction "VSS_PAD_P$79") (pintype "bidirectional"))
      (node (ref "U1") (pin "P$80") (pinfunction "VSS_PAD_P$80") (pintype "bidirectional"))
      (node (ref "U1") (pin "P$81") (pinfunction "VSS_PAD_P$81") (pintype "bidirectional"))
      (node (ref "U1") (pin "P$82") (pinfunction "VSS_PAD_P$82") (pintype "bidirectional"))
      (node (ref "U1") (pin "P$83") (pinfunction "VSS_PAD_P$83") (pintype "bidirectional"))
      (node (ref "U1") (pin "P$84") (pinfunction "VSS_PAD_P$84") (pintype "bidirectional"))
      (node (ref "U1") (pin "P$85") (pinfunction "VSS_PAD_P$85") (pintype "bidirectional"))
      (node (ref "U1") (pin "P$86") (pinfunction "VSS_PAD_P$86") (pintype "bidirectional"))
      (node (ref "U1") (pin "P$87") (pinfunction "VSS_PAD_P$87") (pintype "bidirectional"))
      (node (ref "U1") (pin "P$88") (pinfunction "VSS_PAD_P$88") (pintype "bidirectional"))
      (node (ref "U1") (pin "P$89") (pinfunction "VSS_PAD_P$89") (pintype "bidirectional"))
      (node (ref "U1") (pin "P$90") (pinfunction "VSS_PAD_P$90") (pintype "bidirectional"))
      (node (ref "U1") (pin "P$B7") (pinfunction "VSS_P$B7") (pintype "power_in"))
      (node (ref "U1") (pin "P$F23") (pinfunction "VSS_PA_P$F23") (pintype "bidirectional"))
      (node (ref "U3") (pin "1") (pinfunction "CTG_1") (pintype "power_in"))
      (node (ref "U3") (pin "4") (pinfunction "GND_4") (pintype "power_in"))
      (node (ref "U3") (pin "6") (pinfunction "QSTRT_6") (pintype "input"))
      (node (ref "U3") (pin "9") (pinfunction "EP_9") (pintype "power_in"))
      (node (ref "X1") (pin "2") (pinfunction "2_2") (pintype "passive"))
      (node (ref "X1") (pin "4") (pinfunction "4_4") (pintype "passive"))
    )
    (net (code "14") (name "HAPTIC_EN") (class "Default")
      (node (ref "IC2") (pin "A1") (pinfunction "EN_A1") (pintype "bidirectional"))
      (node (ref "U1") (pin "P$U1") (pinfunction "P0.12_P$U1") (pintype "bidirectional"))
    )
    (net (code "15") (name "IMU_INT1") (class "Default")
      (node (ref "IC3") (pin "5") (pinfunction "INT1_5") (pintype "bidirectional"))
      (node (ref "U1") (pin "P$N1") (pinfunction "P0.08_P$N1") (pintype "bidirectional"))
    )
    (net (code "16") (name "IMU_INT2") (class "Default")
      (node (ref "IC3") (pin "6") (pinfunction "INT2_6") (pintype "bidirectional"))
      (node (ref "U1") (pin "P$P2") (pinfunction "P1.08_P$P2") (pintype "bidirectional"))
    )
    (net (code "17") (name "LX1") (class "Default")
      (node (ref "IC9") (pin "B2") (pinfunction "SW1_1_B2") (pintype "bidirectional"))
      (node (ref "IC9") (pin "B3") (pinfunction "SW1_2_B3") (pintype "bidirectional"))
      (node (ref "L7") (pin "1") (pinfunction "1_1") (pintype "bidirectional"))
    )
    (net (code "18") (name "LX2") (class "Default")
      (node (ref "IC9") (pin "D2") (pinfunction "SW2_1_D2") (pintype "bidirectional"))
      (node (ref "IC9") (pin "D3") (pinfunction "SW2_2_D3") (pintype "bidirectional"))
      (node (ref "L7") (pin "2") (pinfunction "2_2") (pintype "bidirectional"))
    )
    (net (code "19") (name "MOSI") (class "Default")
      (node (ref "J1") (pin "14") (pinfunction "14_14") (pintype "bidirectional"))
      (node (ref "U1") (pin "P$B13") (pinfunction "P0.03/AIN1_P$B13") (pintype "bidirectional"))
    )
    (net (code "20") (name "N$2") (class "Default")
      (node (ref "C6") (pin "1") (pinfunction "1_1") (pintype "passive"))
      (node (ref "U1") (pin "P$W1") (pinfunction "VDD_P$W1") (pintype "power_in"))
      (node (ref "U1") (pin "P$Y2") (pinfunction "VDDH_P$Y2") (pintype "power_in"))
    )
    (net (code "21") (name "Net-(ANT1-FEED)") (class "Default")
      (node (ref "ANT1") (pin "1") (pinfunction "FEED_1") (pintype "input"))
      (node (ref "C22") (pin "1") (pinfunction "1_1") (pintype "passive"))
      (node (ref "C4") (pin "1") (pinfunction "1_1") (pintype "passive"))
      (node (ref "L1") (pin "2") (pinfunction "2_2") (pintype "passive"))
    )
    (net (code "22") (name "Net-(C1-EP-DR-Pad1)") (class "Default")
      (node (ref "C1-EP-DR") (pin "1") (pinfunction "1_1") (pintype "passive"))
      (node (ref "L5") (pin "2") (pinfunction "2_2") (pintype "passive"))
    )
    (net (code "23") (name "Net-(D2-K)") (class "Default")
      (node (ref "C2-EP-DR") (pin "1") (pinfunction "1_1") (pintype "passive"))
      (node (ref "D2") (pin "1") (pinfunction "K_1") (pintype "bidirectional"))
      (node (ref "D4") (pin "2") (pinfunction "A_2") (pintype "bidirectional"))
    )
    (net (code "24") (name "Net-(D5-A)") (class "Default")
      (node (ref "C2-EP-DR") (pin "2") (pinfunction "2_2") (pintype "passive"))
      (node (ref "D5") (pin "2") (pinfunction "A_2") (pintype "bidirectional"))
      (node (ref "L5") (pin "1") (pinfunction "1_1") (pintype "passive"))
      (node (ref "Q3") (pin "3") (pinfunction "D_3") (pintype "bidirectional"))
    )
    (net (code "25") (name "Net-(EPD_C1-Pad2)") (class "Default")
      (node (ref "EPD_C1") (pin "2") (pinfunction "2_2") (pintype "passive"))
      (node (ref "J1") (pin "5") (pinfunction "5_5") (pintype "bidirectional"))
    )
    (net (code "26") (name "Net-(EPD_C2-Pad2)") (class "Default")
      (node (ref "EPD_C2") (pin "2") (pinfunction "2_2") (pintype "passive"))
      (node (ref "J1") (pin "4") (pinfunction "4_4") (pintype "bidirectional"))
    )
    (net (code "27") (name "Net-(EPD_C6-Pad2)") (class "Default")
      (node (ref "EPD_C6") (pin "2") (pinfunction "2_2") (pintype "passive"))
      (node (ref "J1") (pin "18") (pinfunction "18_18") (pintype "bidirectional"))
    )
    (net (code "28") (name "Net-(EPD_C7-Pad1)") (class "Default")
      (node (ref "EPD_C7") (pin "1") (pinfunction "1_1") (pintype "passive"))
      (node (ref "J1") (pin "19") (pinfunction "19_19") (pintype "bidirectional"))
    )
    (net (code "29") (name "Net-(EPD_C8-Pad1)") (class "Default")
      (node (ref "EPD_C8") (pin "1") (pinfunction "1_1") (pintype "passive"))
      (node (ref "J1") (pin "20") (pinfunction "20_20") (pintype "bidirectional"))
    )
    (net (code "30") (name "Net-(EPD_C10-Pad2)") (class "Default")
      (node (ref "EPD_C10") (pin "2") (pinfunction "2_2") (pintype "passive"))
      (node (ref "J1") (pin "22") (pinfunction "22_22") (pintype "bidirectional"))
    )
    (net (code "31") (name "Net-(EPD_C12-Pad1)") (class "Default")
      (node (ref "EPD_C12") (pin "1") (pinfunction "1_1") (pintype "passive"))
      (node (ref "J1") (pin "24") (pinfunction "24_24") (pintype "bidirectional"))
    )
    (net (code "32") (name "Net-(IC1-TS{slash}MR)") (class "Default")
      (node (ref "IC1") (pin "D1") (pinfunction "TS/MR_D1") (pintype "bidirectional"))
      (node (ref "R9") (pin "2") (pinfunction "2_2") (pintype "bidirectional"))
    )
    (net (code "33") (name "Net-(IC2-REG)") (class "Default")
      (node (ref "C32") (pin "2") (pinfunction "2_2") (pintype "passive"))
      (node (ref "IC2") (pin "A2") (pinfunction "REG_A2") (pintype "bidirectional"))
    )
    (net (code "34") (name "Net-(IC3-SDO)") (class "Default")
      (node (ref "IC3") (pin "1") (pinfunction "SDO_1") (pintype "bidirectional"))
      (node (ref "R3") (pin "2") (pinfunction "2_2") (pintype "bidirectional"))
    )
    (net (code "35") (name "Net-(IC9-SCL)") (class "Default")
      (node (ref "IC9") (pin "D1") (pinfunction "SCL_D1") (pintype "bidirectional"))
      (node (ref "R4") (pin "2") (pinfunction "2_2") (pintype "bidirectional"))
    )
    (net (code "36") (name "Net-(IC9-SDA)") (class "Default")
      (node (ref "IC9") (pin "E1") (pinfunction "SDA_E1") (pintype "bidirectional"))
      (node (ref "R2") (pin "2") (pinfunction "2_2") (pintype "bidirectional"))
    )
    (net (code "37") (name "Net-(J4-CC1)") (class "Default")
      (node (ref "J4") (pin "A5") (pinfunction "CC1_A5") (pintype "bidirectional"))
      (node (ref "R1_USB") (pin "2") (pinfunction "2_2") (pintype "bidirectional"))
    )
    (net (code "38") (name "Net-(J4-CC2)") (class "Default")
      (node (ref "J4") (pin "B5") (pinfunction "CC2_B5") (pintype "bidirectional"))
      (node (ref "R2_USB") (pin "1") (pinfunction "1_1") (pintype "bidirectional"))
    )
    (net (code "39") (name "Net-(L2-Pad1)") (class "Default")
      (node (ref "L2") (pin "1") (pinfunction "1_1") (pintype "passive"))
      (node (ref "L3") (pin "1") (pinfunction "1_1") (pintype "passive"))
    )
    (net (code "40") (name "Net-(R1_EP_DR-Pad1)") (class "Default")
      (node (ref "R1_EP_DR") (pin "1") (pinfunction "1_1") (pintype "bidirectional"))
      (node (ref "R_TYPE_SEL") (pin "2") (pinfunction "2_2") (pintype "bidirectional"))
      (node (ref "SJ1") (pin "2") (pinfunction "2_2") (pintype "passive"))
    )
    (net (code "41") (name "Net-(U1-ANT)") (class "Default")
      (node (ref "C3") (pin "1") (pinfunction "1_1") (pintype "passive"))
      (node (ref "L1") (pin "1") (pinfunction "1_1") (pintype "passive"))
      (node (ref "U1") (pin "P$H23") (pinfunction "ANT_P$H23") (pintype "bidirectional"))
    )
    (net (code "42") (name "Net-(U1-DCC)") (class "Default")
      (node (ref "L2") (pin "2") (pinfunction "2_2") (pintype "passive"))
      (node (ref "U1") (pin "P$B3") (pinfunction "DCC_P$B3") (pintype "output"))
    )
    (net (code "43") (name "Net-(U1-DEC1)") (class "Default")
      (node (ref "C5") (pin "1") (pinfunction "1_1") (pintype "passive"))
      (node (ref "U1") (pin "P$C1") (pinfunction "DEC1_P$C1") (pintype "power_in"))
    )
    (net (code "44") (name "Net-(U1-DEC2)") (class "Default")
      (node (ref "C13") (pin "1") (pinfunction "1_1") (pintype "passive"))
      (node (ref "U1") (pin "P$A18") (pinfunction "DEC2_P$A18") (pintype "bidirectional"))
    )
    (net (code "45") (name "Net-(U1-DEC3)") (class "Default")
      (node (ref "C11") (pin "1") (pinfunction "1_1") (pintype "passive"))
      (node (ref "U1") (pin "P$D23") (pinfunction "DEC3_P$D23") (pintype "bidirectional"))
    )
    (net (code "46") (name "Net-(U1-DEC3V3)") (class "Default")
      (node (ref "C20") (pin "1") (pinfunction "1_1") (pintype "passive"))
      (node (ref "U1") (pin "P$AC5") (pinfunction "DEC3V3_P$AC5") (pintype "bidirectional"))
    )
    (net (code "47") (name "Net-(U1-DEC4)") (class "Default")
      (node (ref "C10") (pin "1") (pinfunction "1_1") (pintype "passive"))
      (node (ref "C15") (pin "1") (pinfunction "1_1") (pintype "passive"))
      (node (ref "C16") (pin "1") (pinfunction "1_1") (pintype "passive"))
      (node (ref "L3") (pin "2") (pinfunction "2_2") (pintype "passive"))
      (node (ref "U1") (pin "P$B5") (pinfunction "DEC4_P$B5") (pintype "power_in"))
      (node (ref "U1") (pin "P$E24") (pinfunction "DEC6_P$E24") (pintype "bidirectional"))
    )
    (net (code "48") (name "Net-(U1-DEC5)") (class "Default")
      (node (ref "C9") (pin "1") (pinfunction "1_1") (pintype "passive"))
      (node (ref "U1") (pin "P$N24") (pinfunction "DEC5_P$N24") (pintype "bidirectional"))
    )
    (net (code "49") (name "Net-(U1-P0.00{slash}XL1)") (class "Default")
      (node (ref "C17") (pin "2") (pinfunction "2_2") (pintype "passive"))
      (node (ref "U1") (pin "P$D2") (pinfunction "P0.00/XL1_P$D2") (pintype "bidirectional"))
      (node (ref "X2") (pin "2") (pinfunction "2_2") (pintype "passive"))
    )
    (net (code "50") (name "Net-(U1-P0.01{slash}XL2)") (class "Default")
      (node (ref "C18") (pin "2") (pinfunction "2_2") (pintype "passive"))
      (node (ref "U1") (pin "P$F2") (pinfunction "P0.01/XL2_P$F2") (pintype "bidirectional"))
      (node (ref "X2") (pin "1") (pinfunction "1_1") (pintype "passive"))
    )
    (net (code "51") (name "Net-(U1-XC1)") (class "Default")
      (node (ref "C1") (pin "1") (pinfunction "1_1") (pintype "passive"))
      (node (ref "U1") (pin "P$B24") (pinfunction "XC1_P$B24") (pintype "input"))
      (node (ref "X1") (pin "1") (pinfunction "1_1") (pintype "passive"))
    )
    (net (code "52") (name "Net-(U1-XC2)") (class "Default")
      (node (ref "C2") (pin "1") (pinfunction "1_1") (pintype "passive"))
      (node (ref "U1") (pin "P$A23") (pinfunction "XC2_P$A23") (pintype "output"))
      (node (ref "X1") (pin "3") (pinfunction "3_3") (pintype "passive"))
    )
    (net (code "53") (name "OUT+") (class "Default")
      (node (ref "IC2") (pin "A3") (pinfunction "OUT+_A3") (pintype "bidirectional"))
      (node (ref "TP_OP") (pin "TP") (pinfunction "TP_TP") (pintype "input"))
    )
    (net (code "54") (name "OUT-") (class "Default")
      (node (ref "TP_ON") (pin "TP") (pinfunction "TP_TP") (pintype "input"))
    )
    (net (code "55") (name "P0.04") (class "Default")
      (node (ref "U1") (pin "P$J1") (pinfunction "P0.04/AIN2_P$J1") (pintype "bidirectional"))
    )
    (net (code "56") (name "P0.09") (class "Default")
      (node (ref "U1") (pin "P$L24") (pinfunction "P0.09/NFC1_P$L24") (pintype "bidirectional"))
    )
    (net (code "57") (name "P0.13") (class "Default")
      (node (ref "C30") (pin "2") (pinfunction "2_2") (pintype "passive"))
      (node (ref "R5") (pin "1") (pinfunction "1_1") (pintype "bidirectional"))
      (node (ref "SW1") (pin "2") (pinfunction "2_2") (pintype "passive"))
      (node (ref "U1") (pin "P$AD8") (pinfunction "P0.13_P$AD8") (pintype "bidirectional"))
    )
    (net (code "58") (name "P0.14") (class "Default")
      (node (ref "C31") (pin "2") (pinfunction "2_2") (pintype "passive"))
      (node (ref "R8") (pin "1") (pinfunction "1_1") (pintype "bidirectional"))
      (node (ref "SW2") (pin "2") (pinfunction "2_2") (pintype "passive"))
      (node (ref "U1") (pin "P$AC9") (pinfunction "P0.14_P$AC9") (pintype "bidirectional"))
    )
    (net (code "59") (name "P0.19") (class "Default")
      (node (ref "U1") (pin "P$AC15") (pinfunction "P0.19_P$AC15") (pintype "bidirectional"))
    )
    (net (code "60") (name "P0.20") (class "Default")
      (node (ref "U1") (pin "P$AD16") (pinfunction "P0.20_P$AD16") (pintype "bidirectional"))
    )
    (net (code "61") (name "P0.21") (class "Default")
      (node (ref "U1") (pin "P$AC17") (pinfunction "P0.21_P$AC17") (pintype "bidirectional"))
    )
    (net (code "62") (name "P0.22") (class "Default")
      (node (ref "U1") (pin "P$AD18") (pinfunction "P0.22_P$AD18") (pintype "bidirectional"))
    )
    (net (code "63") (name "P0.23") (class "Default")
      (node (ref "U1") (pin "P$AC19") (pinfunction "P0.23_P$AC19") (pintype "bidirectional"))
    )
    (net (code "64") (name "P0.24") (class "Default")
      (node (ref "U1") (pin "P$AD20") (pinfunction "P0.24_P$AD20") (pintype "bidirectional"))
    )
    (net (code "65") (name "P0.25") (class "Default")
      (node (ref "U1") (pin "P$AC21") (pinfunction "P0.25_P$AC21") (pintype "bidirectional"))
    )
    (net (code "66") (name "P0.26") (class "Default")
      (node (ref "U1") (pin "P$G1") (pinfunction "P0.26_P$G1") (pintype "bidirectional"))
    )
    (net (code "67") (name "P0.27") (class "Default")
      (node (ref "U1") (pin "P$H2") (pinfunction "P0.27_P$H2") (pintype "bidirectional"))
    )
    (net (code "68") (name "P0.28") (class "Default")
      (node (ref "U1") (pin "P$B11") (pinfunction "P0.28/AIN4_P$B11") (pintype "bidirectional"))
    )
    (net (code "69") (name "P0.29") (class "Default")
      (node (ref "U1") (pin "P$A10") (pinfunction "P0.29/AIN5_P$A10") (pintype "bidirectional"))
    )
    (net (code "70") (name "P0.30") (class "Default")
      (node (ref "U1") (pin "P$B9") (pinfunction "P0.30/AIN6_P$B9") (pintype "bidirectional"))
    )
    (net (code "71") (name "P0.31") (class "Default")
      (node (ref "U1") (pin "P$A8") (pinfunction "P0.31/AIN7_P$A8") (pintype "bidirectional"))
    )
    (net (code "72") (name "P1.01") (class "Default")
      (node (ref "DMG2305UX-7") (pin "1") (pinfunction "G_1") (pintype "bidirectional"))
      (node (ref "R_PWR_EPD") (pin "1") (pinfunction "1_1") (pintype "bidirectional"))
      (node (ref "U1") (pin "P$Y23") (pinfunction "P1.01_P$Y23") (pintype "bidirectional"))
    )
    (net (code "73") (name "P1.02") (class "Default")
      (node (ref "C29") (pin "2") (pinfunction "2_2") (pintype "passive"))
      (node (ref "R7") (pin "1") (pinfunction "1_1") (pintype "bidirectional"))
      (node (ref "SW3") (pin "2") (pinfunction "2_2") (pintype "passive"))
      (node (ref "U1") (pin "P$W24") (pinfunction "P1.02_P$W24") (pintype "bidirectional"))
    )
    (net (code "74") (name "P1.03") (class "Default")
      (node (ref "U1") (pin "P$V23") (pinfunction "P1.03_P$V23") (pintype "bidirectional"))
    )
    (net (code "75") (name "P1.04") (class "Default")
      (node (ref "U1") (pin "P$U24") (pinfunction "P1.04_P$U24") (pintype "bidirectional"))
    )
    (net (code "76") (name "P1.05") (class "Default")
      (node (ref "U1") (pin "P$T23") (pinfunction "P1.05_P$T23") (pintype "bidirectional"))
    )
    (net (code "77") (name "P1.06") (class "Default")
      (node (ref "U1") (pin "P$R24") (pinfunction "P1.06_P$R24") (pintype "bidirectional"))
    )
    (net (code "78") (name "P1.07") (class "Default")
      (node (ref "U1") (pin "P$P23") (pinfunction "P1.07_P$P23") (pintype "bidirectional"))
    )
    (net (code "79") (name "P1.09") (class "Default")
      (node (ref "U1") (pin "P$R1") (pinfunction "P1.09_P$R1") (pintype "bidirectional"))
    )
    (net (code "80") (name "P1.10") (class "Default")
      (node (ref "U1") (pin "P$A20") (pinfunction "P1.10_P$A20") (pintype "bidirectional"))
    )
    (net (code "81") (name "P1.11") (class "Default")
      (node (ref "U1") (pin "P$B19") (pinfunction "P1.11_P$B19") (pintype "bidirectional"))
    )
    (net (code "82") (name "P1.12") (class "Default")
      (node (ref "U1") (pin "P$B17") (pinfunction "P1.12_P$B17") (pintype "bidirectional"))
    )
    (net (code "83") (name "P1.13") (class "Default")
      (node (ref "U1") (pin "P$A16") (pinfunction "P1.13_P$A16") (pintype "bidirectional"))
    )
    (net (code "84") (name "P1.14") (class "Default")
      (node (ref "U1") (pin "P$B15") (pinfunction "P1.14_P$B15") (pintype "bidirectional"))
    )
    (net (code "85") (name "P1.15") (class "Default")
      (node (ref "U1") (pin "P$A14") (pinfunction "P1.15_P$A14") (pintype "bidirectional"))
    )
    (net (code "86") (name "PMIC_INT") (class "Default")
      (node (ref "IC1") (pin "A1") (pinfunction "~{INT}_A1") (pintype "bidirectional"))
      (node (ref "U1") (pin "P$T2") (pinfunction "P0.11_P$T2") (pintype "bidirectional"))
    )
    (net (code "87") (name "PREVGH") (class "Default")
      (node (ref "D5") (pin "1") (pinfunction "K_1") (pintype "bidirectional"))
      (node (ref "EPD_C9") (pin "1") (pinfunction "1_1") (pintype "passive"))
      (node (ref "J1") (pin "21") (pinfunction "21_21") (pintype "bidirectional"))
    )
    (net (code "88") (name "PREVGL") (class "Default")
      (node (ref "D2") (pin "2") (pinfunction "A_2") (pintype "bidirectional"))
      (node (ref "EPD_C11") (pin "1") (pinfunction "1_1") (pintype "passive"))
      (node (ref "J1") (pin "23") (pinfunction "23_23") (pintype "bidirectional"))
    )
    (net (code "89") (name "RESE") (class "Default")
      (node (ref "J1") (pin "3") (pinfunction "3_3") (pintype "bidirectional"))
      (node (ref "Q3") (pin "2") (pinfunction "S_2") (pintype "bidirectional"))
      (node (ref "R1_EP_DR") (pin "2") (pinfunction "2_2") (pintype "bidirectional"))
    )
    (net (code "90") (name "RESET") (class "Default")
      (node (ref "J2") (pin "6") (pinfunction "6_6") (pintype "bidirectional"))
      (node (ref "TP_RESET") (pin "TP") (pinfunction "TP_TP") (pintype "input"))
      (node (ref "U1") (pin "P$AC13") (pinfunction "P0.18/RESET_P$AC13") (pintype "bidirectional"))
    )
    (net (code "91") (name "SCK") (class "Default")
      (node (ref "J1") (pin "13") (pinfunction "13_13") (pintype "bidirectional"))
      (node (ref "U1") (pin "P$A12") (pinfunction "P0.02/AIN0_P$A12") (pintype "bidirectional"))
    )
    (net (code "92") (name "SCL") (class "Default")
      (node (ref "IC1") (pin "B1") (pinfunction "SCL_B1") (pintype "bidirectional"))
      (node (ref "IC2") (pin "C1") (pinfunction "SCL_C1") (pintype "bidirectional"))
      (node (ref "IC3") (pin "12") (pinfunction "SCX_12") (pintype "bidirectional"))
      (node (ref "R17") (pin "2") (pinfunction "2_2") (pintype "bidirectional"))
      (node (ref "R4") (pin "1") (pinfunction "1_1") (pintype "bidirectional"))
      (node (ref "TP3") (pin "TP") (pinfunction "TP_TP") (pintype "input"))
      (node (ref "U1") (pin "P$M2") (pinfunction "P0.07_P$M2") (pintype "bidirectional"))
      (node (ref "U3") (pin "7") (pinfunction "SCL_7") (pintype "input"))
    )
    (net (code "93") (name "SDA") (class "Default")
      (node (ref "IC1") (pin "C1") (pinfunction "SDA_C1") (pintype "bidirectional"))
      (node (ref "IC2") (pin "B2") (pinfunction "SDA_B2") (pintype "bidirectional"))
      (node (ref "IC3") (pin "2") (pinfunction "SDX_2") (pintype "bidirectional"))
      (node (ref "R18") (pin "2") (pinfunction "2_2") (pintype "bidirectional"))
      (node (ref "R2") (pin "1") (pinfunction "1_1") (pintype "bidirectional"))
      (node (ref "TP4") (pin "TP") (pinfunction "TP_TP") (pintype "input"))
      (node (ref "U1") (pin "P$L1") (pinfunction "P0.06_P$L1") (pintype "bidirectional"))
      (node (ref "U3") (pin "8") (pinfunction "SDA_8") (pintype "bidirectional"))
    )
    (net (code "94") (name "SWDCLK") (class "Default")
      (node (ref "J2") (pin "4") (pinfunction "4_4") (pintype "bidirectional"))
      (node (ref "TP_SWDCLK") (pin "TP") (pinfunction "TP_TP") (pintype "input"))
      (node (ref "U1") (pin "P$AA24") (pinfunction "SWDCLK_P$AA24") (pintype "input"))
    )
    (net (code "95") (name "SWDIO") (class "Default")
      (node (ref "J2") (pin "2") (pinfunction "2_2") (pintype "bidirectional"))
      (node (ref "TP_SWDIO") (pin "TP") (pinfunction "TP_TP") (pintype "input"))
      (node (ref "U1") (pin "P$AC24") (pinfunction "SWDIO_P$AC24") (pintype "bidirectional"))
    )
    (net (code "96") (name "SWO") (class "Default")
      (node (ref "TP_SWO") (pin "TP") (pinfunction "TP_TP") (pintype "input"))
      (node (ref "U1") (pin "P$AD22") (pinfunction "P1.00_P$AD22") (pintype "bidirectional"))
    )
    (net (code "97") (name "VBAT") (class "Default")
      (node (ref "C27") (pin "2") (pinfunction "2_2") (pintype "passive"))
      (node (ref "C37") (pin "2") (pinfunction "2_2") (pintype "passive"))
      (node (ref "IC1") (pin "C2") (pinfunction "BAT_C2") (pintype "bidirectional"))
      (node (ref "TP_VBAT") (pin "TP") (pinfunction "TP_TP") (pintype "input"))
      (node (ref "U3") (pin "2") (pinfunction "CELL_2") (pintype "power_in"))
      (node (ref "U3") (pin "3") (pinfunction "VDD_3") (pintype "power_in"))
    )
    (net (code "98") (name "VBUS") (class "Default")
      (node (ref "C21") (pin "1") (pinfunction "1_1") (pintype "passive"))
      (node (ref "C38") (pin "2") (pinfunction "2_2") (pintype "passive"))
      (node (ref "C42") (pin "1") (pinfunction "1_1") (pintype "passive"))
      (node (ref "C43") (pin "1") (pinfunction "1_1") (pintype "passive"))
      (node (ref "D3") (pin "5") (pinfunction "VBUS_5") (pintype "bidirectional"))
      (node (ref "IC1") (pin "A2") (pinfunction "IN_A2") (pintype "bidirectional"))
      (node (ref "J4") (pin "A4_B9") (pinfunction "VBUS_A4_B9") (pintype "power_in"))
      (node (ref "J4") (pin "A9_B4") (pinfunction "VBUS_A9_B4") (pintype "power_in"))
      (node (ref "U1") (pin "P$AD2") (pinfunction "VBUS_P$AD2") (pintype "power_in"))
    )
    (net (code "99") (name "VREG") (class "Default")
      (node (ref "C23") (pin "2") (pinfunction "2_2") (pintype "passive"))
      (node (ref "C24") (pin "2") (pinfunction "2_2") (pintype "passive"))
      (node (ref "C39") (pin "1") (pinfunction "1_1") (pintype "passive"))
      (node (ref "IC1") (pin "B2") (pinfunction "SYS_B2") (pintype "bidirectional"))
      (node (ref "IC9") (pin "A1") (pinfunction "EN_A1") (pintype "bidirectional"))
      (node (ref "IC9") (pin "A2") (pinfunction "VIN_1_A2") (pintype "bidirectional"))
      (node (ref "IC9") (pin "A3") (pinfunction "VIN_2_A3") (pintype "bidirectional"))
      (node (ref "TP_VREG") (pin "TP") (pinfunction "TP_TP") (pintype "input"))
    )
    (net (code "100") (name "unconnected-(ANT1-NC-Pad2)") (class "Default")
      (node (ref "ANT1") (pin "2") (pinfunction "NC_2") (pintype "no_connect"))
    )
    (net (code "101") (name "unconnected-(IC2-OUT--PadC3)") (class "Default")
      (node (ref "IC2") (pin "C3") (pinfunction "OUT-_C3") (pintype "bidirectional"))
    )
    (net (code "102") (name "unconnected-(IC3-ASCL-Pad11)") (class "Default")
      (node (ref "IC3") (pin "11") (pinfunction "ASCL_11") (pintype "bidirectional"))
    )
    (net (code "103") (name "unconnected-(IC3-ASDA-Pad4)") (class "Default")
      (node (ref "IC3") (pin "4") (pinfunction "ASDA_4") (pintype "bidirectional"))
    )
    (net (code "104") (name "unconnected-(J1-Pad1)") (class "Default")
      (node (ref "J1") (pin "1") (pinfunction "1_1") (pintype "bidirectional"))
    )
    (net (code "105") (name "unconnected-(J1-Pad6)") (class "Default")
      (node (ref "J1") (pin "6") (pinfunction "6_6") (pintype "bidirectional"))
    )
    (net (code "106") (name "unconnected-(J1-Pad7)") (class "Default")
      (node (ref "J1") (pin "7") (pinfunction "7_7") (pintype "bidirectional"))
    )
    (net (code "107") (name "unconnected-(J4-SBU1-PadA8)") (class "Default")
      (node (ref "J4") (pin "A8") (pinfunction "SBU1_A8") (pintype "bidirectional"))
    )
    (net (code "108") (name "unconnected-(J4-SBU2-PadB8)") (class "Default")
      (node (ref "J4") (pin "B8") (pinfunction "SBU2_B8") (pintype "bidirectional"))
    )
    (net (code "109") (name "unconnected-(U1-DCCH-PadP$AB2)") (class "Default")
      (node (ref "U1") (pin "P$AB2") (pinfunction "DCCH_P$AB2") (pintype "bidirectional"))
    )
  )
)
